# TI74_RAM.net
KiCad netlist of a schematic drawn in EAGLE
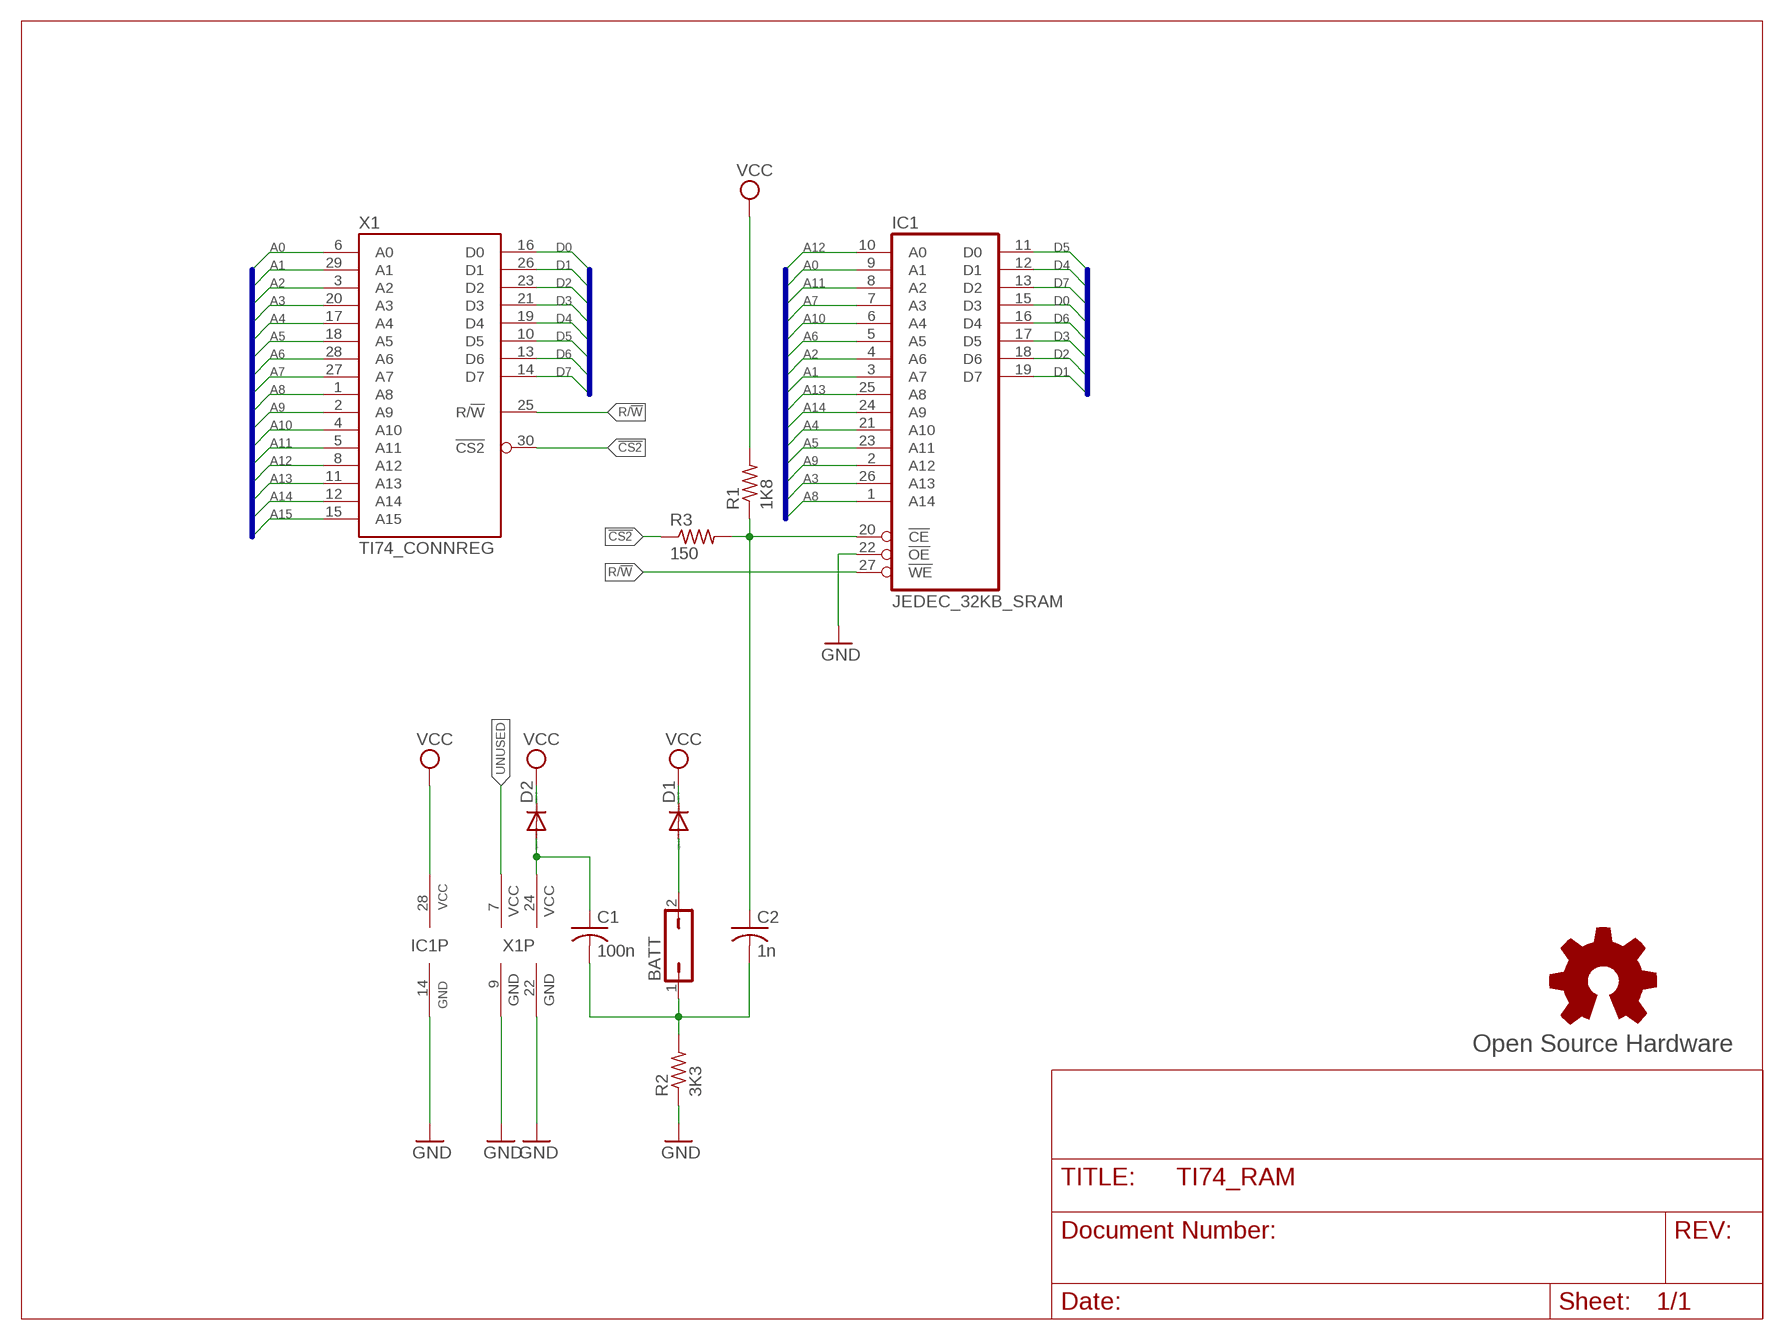
[diagram p0: schematic, sheet 1]

(export (version "E")
  (design (tool "Eeschema 10.0.6"))
  (components
    (comp (ref "BATT")
      (value "JP1Q")
      (footprint "eagle-import:JP1")
      (libsource (lib "eagle-import") (part "JP1Q"))
    )
    (comp (ref "C1")
      (value "100n")
      (footprint "eagle-import:C0603")
      (libsource (lib "eagle-import") (part "C-USC0603"))
    )
    (comp (ref "C2")
      (value "1n")
      (footprint "eagle-import:C0603")
      (libsource (lib "eagle-import") (part "C-USC0603"))
    )
    (comp (ref "D1")
      (value "DIODE-SOD323-W")
      (footprint "eagle-import:SOD323-W")
      (libsource (lib "eagle-import") (part "DIODE-SOD323-W"))
    )
    (comp (ref "D2")
      (value "DIODE-SOD323-W")
      (footprint "eagle-import:SOD323-W")
      (libsource (lib "eagle-import") (part "DIODE-SOD323-W"))
    )
    (comp (ref "GOLD_ORB_SM1")
      (value "Open Source Hardware")
      (footprint "eagle-import:OSHW_5MM")
      (libsource (lib "eagle-import") (part "OSHWLOGOLOGO5MM"))
    )
    (comp (ref "IC1")
      (value "JEDEC_32KB_SRAM")
      (footprint "eagle-import:SO28L")
      (fields (field (name "MPN") "CY62256VNLL-70SNXI"))
      (libsource (lib "eagle-import") (part "JEDEC_32KB_SRAM"))
    )
    (comp (ref "R1")
      (value "1K8")
      (footprint "eagle-import:R0603")
      (libsource (lib "eagle-import") (part "R-US_R0603"))
    )
    (comp (ref "R2")
      (value "3K3")
      (footprint "eagle-import:R0603")
      (libsource (lib "eagle-import") (part "R-US_R0603"))
    )
    (comp (ref "R3")
      (value "150")
      (footprint "eagle-import:R0603")
      (libsource (lib "eagle-import") (part "R-US_R0603"))
    )
    (comp (ref "X1")
      (value "TI74_CONNREG")
      (footprint "eagle-import:MA050-15-2SHORT")
      (libsource (lib "eagle-import") (part "TI74_CONNREG"))
    )
  )
  (nets
    (net (code "1") (name "/A0") (class "Default")
      (node (ref "IC1") (pin "9") (pinfunction "A1_9") (pintype "input"))
      (node (ref "X1") (pin "6") (pinfunction "A0_6") (pintype "bidirectional"))
    )
    (net (code "2") (name "/A1") (class "Default")
      (node (ref "IC1") (pin "3") (pinfunction "A7_3") (pintype "input"))
      (node (ref "X1") (pin "29") (pinfunction "A1_29") (pintype "bidirectional"))
    )
    (net (code "3") (name "/A2") (class "Default")
      (node (ref "IC1") (pin "4") (pinfunction "A6_4") (pintype "input"))
      (node (ref "X1") (pin "3") (pinfunction "A2_3") (pintype "bidirectional"))
    )
    (net (code "4") (name "/A3") (class "Default")
      (node (ref "IC1") (pin "26") (pinfunction "A13_26") (pintype "input"))
      (node (ref "X1") (pin "20") (pinfunction "A3_20") (pintype "bidirectional"))
    )
    (net (code "5") (name "/A4") (class "Default")
      (node (ref "IC1") (pin "21") (pinfunction "A10_21") (pintype "input"))
      (node (ref "X1") (pin "17") (pinfunction "A4_17") (pintype "bidirectional"))
    )
    (net (code "6") (name "/A5") (class "Default")
      (node (ref "IC1") (pin "23") (pinfunction "A11_23") (pintype "input"))
      (node (ref "X1") (pin "18") (pinfunction "A5_18") (pintype "bidirectional"))
    )
    (net (code "7") (name "/A6") (class "Default")
      (node (ref "IC1") (pin "5") (pinfunction "A5_5") (pintype "input"))
      (node (ref "X1") (pin "28") (pinfunction "A6_28") (pintype "bidirectional"))
    )
    (net (code "8") (name "/A7") (class "Default")
      (node (ref "IC1") (pin "7") (pinfunction "A3_7") (pintype "input"))
      (node (ref "X1") (pin "27") (pinfunction "A7_27") (pintype "bidirectional"))
    )
    (net (code "9") (name "/A8") (class "Default")
      (node (ref "IC1") (pin "1") (pinfunction "A14_1") (pintype "input"))
      (node (ref "X1") (pin "1") (pinfunction "A8_1") (pintype "bidirectional"))
    )
    (net (code "10") (name "/A9") (class "Default")
      (node (ref "IC1") (pin "2") (pinfunction "A12_2") (pintype "input"))
      (node (ref "X1") (pin "2") (pinfunction "A9_2") (pintype "bidirectional"))
    )
    (net (code "11") (name "/A10") (class "Default")
      (node (ref "IC1") (pin "6") (pinfunction "A4_6") (pintype "input"))
      (node (ref "X1") (pin "4") (pinfunction "A10_4") (pintype "bidirectional"))
    )
    (net (code "12") (name "/A11") (class "Default")
      (node (ref "IC1") (pin "8") (pinfunction "A2_8") (pintype "input"))
      (node (ref "X1") (pin "5") (pinfunction "A11_5") (pintype "bidirectional"))
    )
    (net (code "13") (name "/A12") (class "Default")
      (node (ref "IC1") (pin "10") (pinfunction "A0_10") (pintype "input"))
      (node (ref "X1") (pin "8") (pinfunction "A12_8") (pintype "bidirectional"))
    )
    (net (code "14") (name "/A13") (class "Default")
      (node (ref "IC1") (pin "25") (pinfunction "A8_25") (pintype "input"))
      (node (ref "X1") (pin "11") (pinfunction "A13_11") (pintype "bidirectional"))
    )
    (net (code "15") (name "/A14") (class "Default")
      (node (ref "IC1") (pin "24") (pinfunction "A9_24") (pintype "input"))
      (node (ref "X1") (pin "12") (pinfunction "A14_12") (pintype "bidirectional"))
    )
    (net (code "16") (name "/A15") (class "Default")
      (node (ref "X1") (pin "15") (pinfunction "A15_15") (pintype "bidirectional"))
    )
    (net (code "17") (name "/D0") (class "Default")
      (node (ref "IC1") (pin "15") (pinfunction "D3_15") (pintype "bidirectional"))
      (node (ref "X1") (pin "16") (pinfunction "D0_16") (pintype "bidirectional"))
    )
    (net (code "18") (name "/D1") (class "Default")
      (node (ref "IC1") (pin "19") (pinfunction "D7_19") (pintype "bidirectional"))
      (node (ref "X1") (pin "26") (pinfunction "D1_26") (pintype "bidirectional"))
    )
    (net (code "19") (name "/D2") (class "Default")
      (node (ref "IC1") (pin "18") (pinfunction "D6_18") (pintype "bidirectional"))
      (node (ref "X1") (pin "23") (pinfunction "D2_23") (pintype "bidirectional"))
    )
    (net (code "20") (name "/D3") (class "Default")
      (node (ref "IC1") (pin "17") (pinfunction "D5_17") (pintype "bidirectional"))
      (node (ref "X1") (pin "21") (pinfunction "D3_21") (pintype "bidirectional"))
    )
    (net (code "21") (name "/D4") (class "Default")
      (node (ref "IC1") (pin "12") (pinfunction "D1_12") (pintype "bidirectional"))
      (node (ref "X1") (pin "19") (pinfunction "D4_19") (pintype "bidirectional"))
    )
    (net (code "22") (name "/D5") (class "Default")
      (node (ref "IC1") (pin "11") (pinfunction "D0_11") (pintype "bidirectional"))
      (node (ref "X1") (pin "10") (pinfunction "D5_10") (pintype "bidirectional"))
    )
    (net (code "23") (name "/D6") (class "Default")
      (node (ref "IC1") (pin "16") (pinfunction "D4_16") (pintype "bidirectional"))
      (node (ref "X1") (pin "13") (pinfunction "D6_13") (pintype "bidirectional"))
    )
    (net (code "24") (name "/D7") (class "Default")
      (node (ref "IC1") (pin "13") (pinfunction "D2_13") (pintype "bidirectional"))
      (node (ref "X1") (pin "14") (pinfunction "D7_14") (pintype "bidirectional"))
    )
    (net (code "25") (name "/R{slash}~{W}") (class "Default")
      (node (ref "IC1") (pin "27") (pinfunction "~{WE}_27") (pintype "input"))
      (node (ref "X1") (pin "25") (pinfunction "R/~{W}_25") (pintype "bidirectional"))
    )
    (net (code "26") (name "/~{CS2}") (class "Default")
      (node (ref "R3") (pin "1") (pinfunction "1_1") (pintype "passive"))
      (node (ref "X1") (pin "30") (pinfunction "~{CS2}_30") (pintype "bidirectional"))
    )
    (net (code "27") (name "GND") (class "Default")
      (node (ref "IC1") (pin "14") (pinfunction "GND_14") (pintype "power_in"))
      (node (ref "IC1") (pin "22") (pinfunction "~{OE}_22") (pintype "input"))
      (node (ref "R2") (pin "1") (pinfunction "1_1") (pintype "passive"))
      (node (ref "X1") (pin "22") (pinfunction "GND_22") (pintype "power_in"))
      (node (ref "X1") (pin "9") (pinfunction "GND_9") (pintype "power_in"))
    )
    (net (code "28") (name "Net-(BATT-Pad1)") (class "Default")
      (node (ref "BATT") (pin "1") (pinfunction "1_1") (pintype "passive"))
      (node (ref "C1") (pin "2") (pinfunction "2_2") (pintype "passive"))
      (node (ref "C2") (pin "2") (pinfunction "2_2") (pintype "passive"))
      (node (ref "R2") (pin "2") (pinfunction "2_2") (pintype "passive"))
    )
    (net (code "29") (name "Net-(BATT-Pad2)") (class "Default")
      (node (ref "BATT") (pin "2") (pinfunction "2_2") (pintype "passive"))
      (node (ref "D1") (pin "A") (pinfunction "A_A") (pintype "passive"))
    )
    (net (code "30") (name "Net-(IC1A-~{CE})") (class "Default")
      (node (ref "C2") (pin "1") (pinfunction "1_1") (pintype "passive"))
      (node (ref "IC1") (pin "20") (pinfunction "~{CE}_20") (pintype "input"))
      (node (ref "R1") (pin "1") (pinfunction "1_1") (pintype "passive"))
      (node (ref "R3") (pin "2") (pinfunction "2_2") (pintype "passive"))
    )
    (net (code "31") (name "Net-(X1B-VCC_RAM)") (class "Default")
      (node (ref "C1") (pin "1") (pinfunction "1_1") (pintype "passive"))
      (node (ref "D2") (pin "A") (pinfunction "A_A") (pintype "passive"))
      (node (ref "X1") (pin "24") (pinfunction "VCC_RAM_24") (pintype "power_in"))
    )
    (net (code "32") (name "UNUSED") (class "Default")
      (node (ref "X1") (pin "7") (pinfunction "VCC_7") (pintype "power_in"))
    )
    (net (code "33") (name "VCC") (class "Default")
      (node (ref "D1") (pin "C") (pinfunction "C_C") (pintype "passive"))
      (node (ref "D2") (pin "C") (pinfunction "C_C") (pintype "passive"))
      (node (ref "IC1") (pin "28") (pinfunction "VCC_28") (pintype "power_in"))
      (node (ref "R1") (pin "2") (pinfunction "2_2") (pintype "passive"))
    )
  )
)
